# working.net
KiCad netlist of a schematic drawn in EAGLE
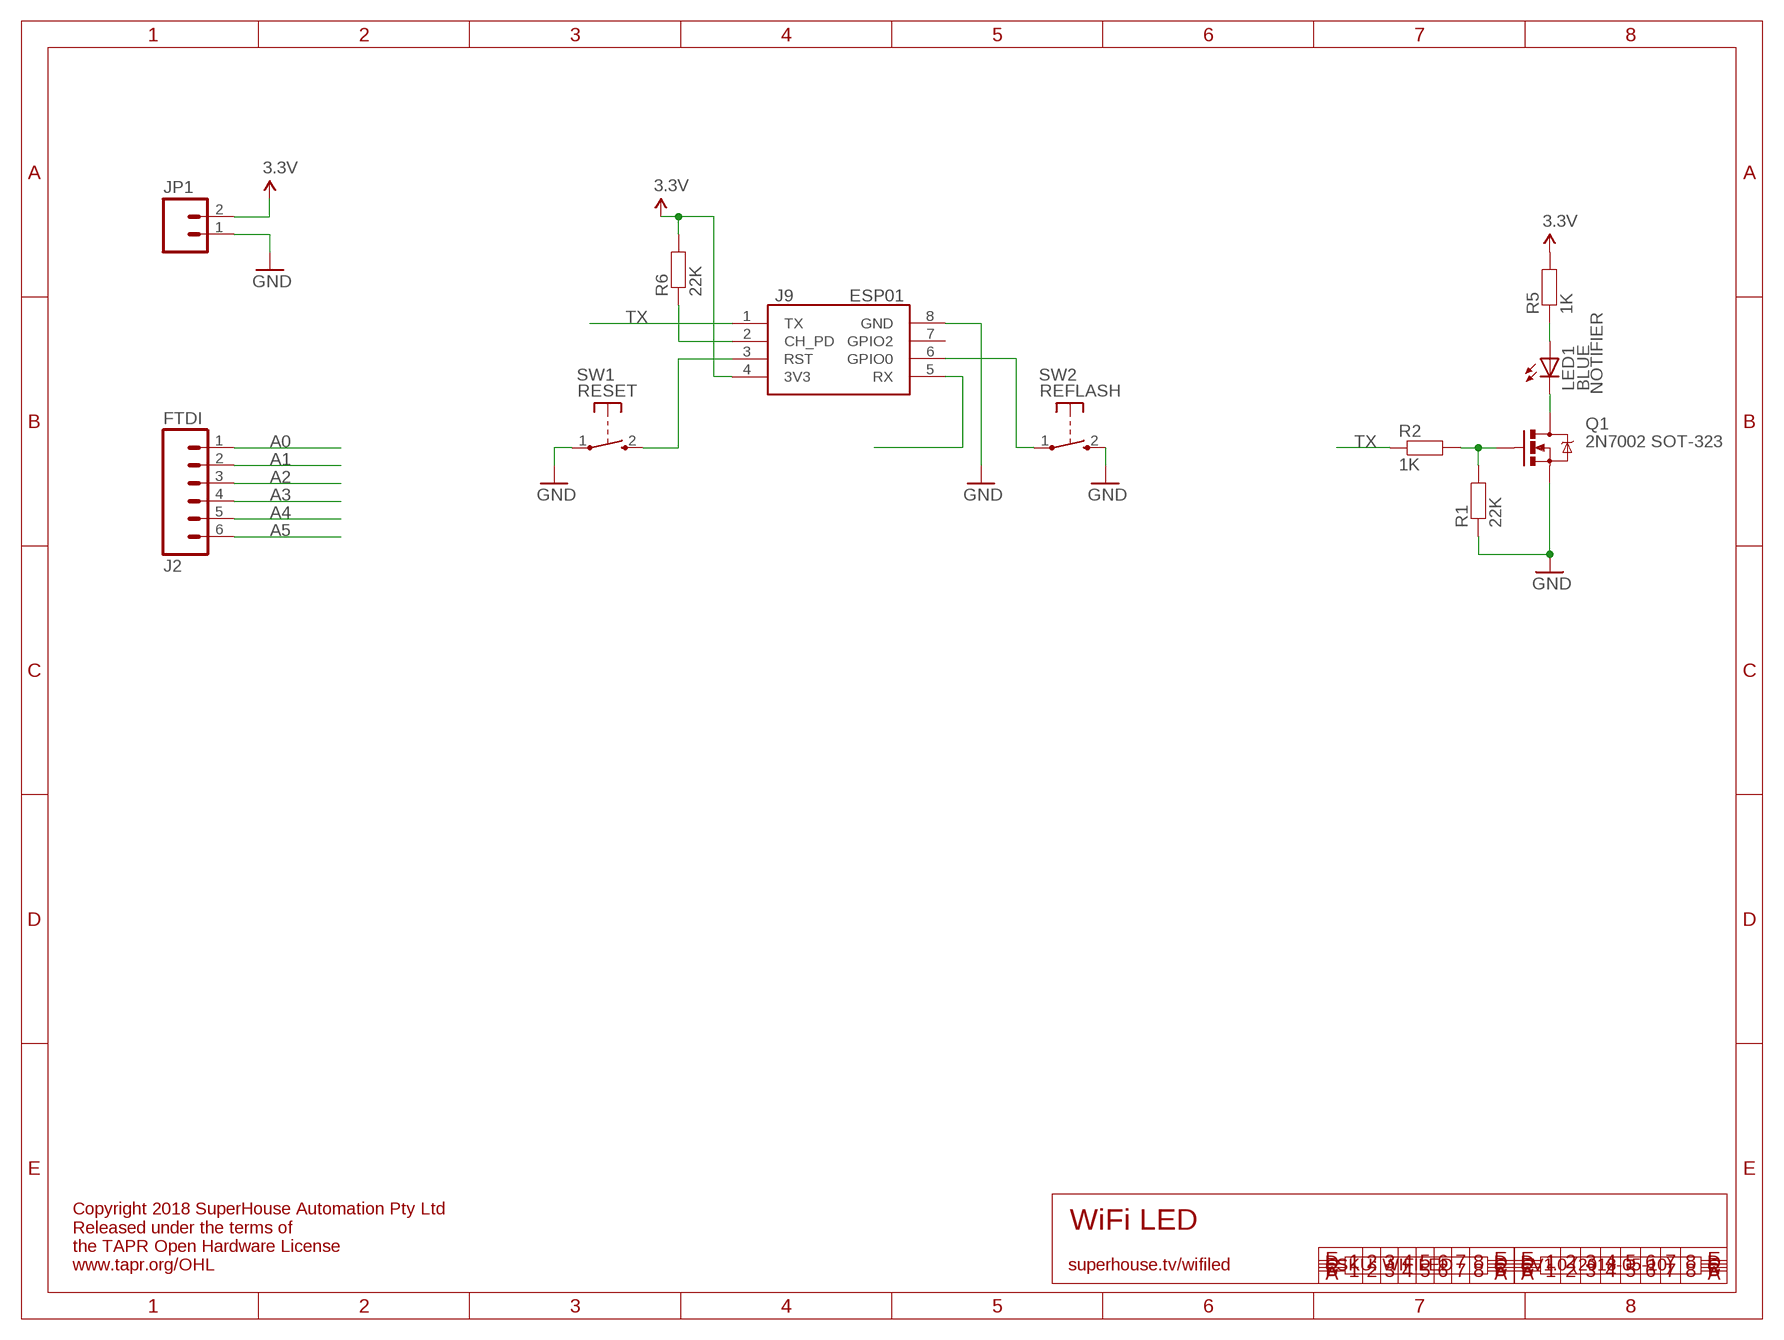
[diagram p0: schematic, sheet 1]

(export (version "E")
  (design (tool "Eeschema 10.0.6"))
  (components
    (comp (ref "J2")
      (value "FTDI")
      (footprint "eagle-import:1X06")
      (libsource (lib "eagle-import") (part "M06SIP"))
    )
    (comp (ref "J9")
      (value "ESP01")
      (footprint "eagle-import:ESP01")
      (libsource (lib "eagle-import") (part "ESP01"))
    )
    (comp (ref "JP1")
      (value "M02PTH")
      (footprint "eagle-import:1X02")
      (libsource (lib "eagle-import") (part "M02PTH"))
    )
    (comp (ref "LED1")
      (value "BLUE")
      (footprint "eagle-import:LED-0603")
      (libsource (lib "eagle-import") (part "LED0603"))
    )
    (comp (ref "Q1")
      (value "2N7002 SOT-323")
      (footprint "eagle-import:SOT32-3")
      (libsource (lib "eagle-import") (part "MOSFET-NSOT-323"))
    )
    (comp (ref "R1")
      (value "22K")
      (footprint "eagle-import:0603")
      (libsource (lib "eagle-import") (part "RESISTOR0603"))
    )
    (comp (ref "R2")
      (value "1K")
      (footprint "eagle-import:0603")
      (libsource (lib "eagle-import") (part "RESISTOR0603"))
    )
    (comp (ref "R5")
      (value "1K")
      (footprint "eagle-import:0603")
      (libsource (lib "eagle-import") (part "RESISTOR0603"))
    )
    (comp (ref "R6")
      (value "22K")
      (footprint "eagle-import:0603")
      (libsource (lib "eagle-import") (part "RESISTOR0603"))
    )
    (comp (ref "SW1")
      (value "RESET")
      (footprint "eagle-import:TACTILE_SWITCH_SMD_2PIN_TINY")
      (libsource (lib "eagle-import") (part "TAC_SWITCH_2PIN"))
    )
    (comp (ref "SW2")
      (value "REFLASH")
      (footprint "eagle-import:TACTILE_SWITCH_SMD_2PIN_TINY")
      (libsource (lib "eagle-import") (part "TAC_SWITCH_2PIN"))
    )
  )
  (nets
    (net (code "1") (name "/A0") (class "Default")
      (node (ref "J2") (pin "1") (pinfunction "1_1") (pintype "passive"))
    )
    (net (code "2") (name "/A1") (class "Default")
      (node (ref "J2") (pin "2") (pinfunction "2_2") (pintype "passive"))
    )
    (net (code "3") (name "/A2") (class "Default")
      (node (ref "J2") (pin "3") (pinfunction "3_3") (pintype "passive"))
    )
    (net (code "4") (name "/A3") (class "Default")
      (node (ref "J2") (pin "4") (pinfunction "4_4") (pintype "passive"))
    )
    (net (code "5") (name "/A4") (class "Default")
      (node (ref "J2") (pin "5") (pinfunction "5_5") (pintype "passive"))
    )
    (net (code "6") (name "/A5") (class "Default")
      (node (ref "J2") (pin "6") (pinfunction "6_6") (pintype "passive"))
    )
    (net (code "7") (name "/TX") (class "Default")
      (node (ref "J9") (pin "1") (pinfunction "TX_1") (pintype "bidirectional"))
      (node (ref "R2") (pin "1") (pinfunction "1_1") (pintype "passive"))
    )
    (net (code "8") (name "3.3V") (class "Default")
      (node (ref "J9") (pin "4") (pinfunction "3V3_4") (pintype "bidirectional"))
      (node (ref "JP1") (pin "2") (pinfunction "2_2") (pintype "passive"))
      (node (ref "R5") (pin "2") (pinfunction "2_2") (pintype "passive"))
      (node (ref "R6") (pin "2") (pinfunction "2_2") (pintype "passive"))
    )
    (net (code "9") (name "GND") (class "Default")
      (node (ref "J9") (pin "8") (pinfunction "GND_8") (pintype "bidirectional"))
      (node (ref "JP1") (pin "1") (pinfunction "1_1") (pintype "passive"))
      (node (ref "Q1") (pin "2") (pinfunction "S_2") (pintype "passive"))
      (node (ref "R1") (pin "1") (pinfunction "1_1") (pintype "passive"))
      (node (ref "SW1") (pin "1") (pinfunction "P_1") (pintype "passive"))
      (node (ref "SW2") (pin "2") (pinfunction "S_2") (pintype "passive"))
    )
    (net (code "10") (name "Net-(J9-CH_PD)") (class "Default")
      (node (ref "J9") (pin "2") (pinfunction "CH_PD_2") (pintype "bidirectional"))
      (node (ref "R6") (pin "1") (pinfunction "1_1") (pintype "passive"))
    )
    (net (code "11") (name "Net-(J9-GPIO0)") (class "Default")
      (node (ref "J9") (pin "6") (pinfunction "GPIO0_6") (pintype "bidirectional"))
      (node (ref "SW2") (pin "1") (pinfunction "P_1") (pintype "passive"))
    )
    (net (code "12") (name "Net-(J9-RST)") (class "Default")
      (node (ref "J9") (pin "3") (pinfunction "RST_3") (pintype "bidirectional"))
      (node (ref "SW1") (pin "2") (pinfunction "S_2") (pintype "passive"))
    )
    (net (code "13") (name "Net-(LED1-PadA)") (class "Default")
      (node (ref "LED1") (pin "A") (pinfunction "A_A") (pintype "passive"))
      (node (ref "R5") (pin "1") (pinfunction "1_1") (pintype "passive"))
    )
    (net (code "14") (name "Net-(Q1-D)") (class "Default")
      (node (ref "LED1") (pin "C") (pinfunction "C_C") (pintype "passive"))
      (node (ref "Q1") (pin "3") (pinfunction "D_3") (pintype "passive"))
    )
    (net (code "15") (name "Net-(Q1-G)") (class "Default")
      (node (ref "Q1") (pin "1") (pinfunction "G_1") (pintype "passive"))
      (node (ref "R1") (pin "2") (pinfunction "2_2") (pintype "passive"))
      (node (ref "R2") (pin "2") (pinfunction "2_2") (pintype "passive"))
    )
    (net (code "16") (name "unconnected-(J9-GPIO2-Pad7)") (class "Default")
      (node (ref "J9") (pin "7") (pinfunction "GPIO2_7") (pintype "bidirectional"))
    )
    (net (code "17") (name "unconnected-(J9-RX-Pad5)") (class "Default")
      (node (ref "J9") (pin "5") (pinfunction "RX_5") (pintype "bidirectional"))
    )
  )
)
